# Current_control_iron.net
KiCad netlist of a schematic drawn in Altium Designer
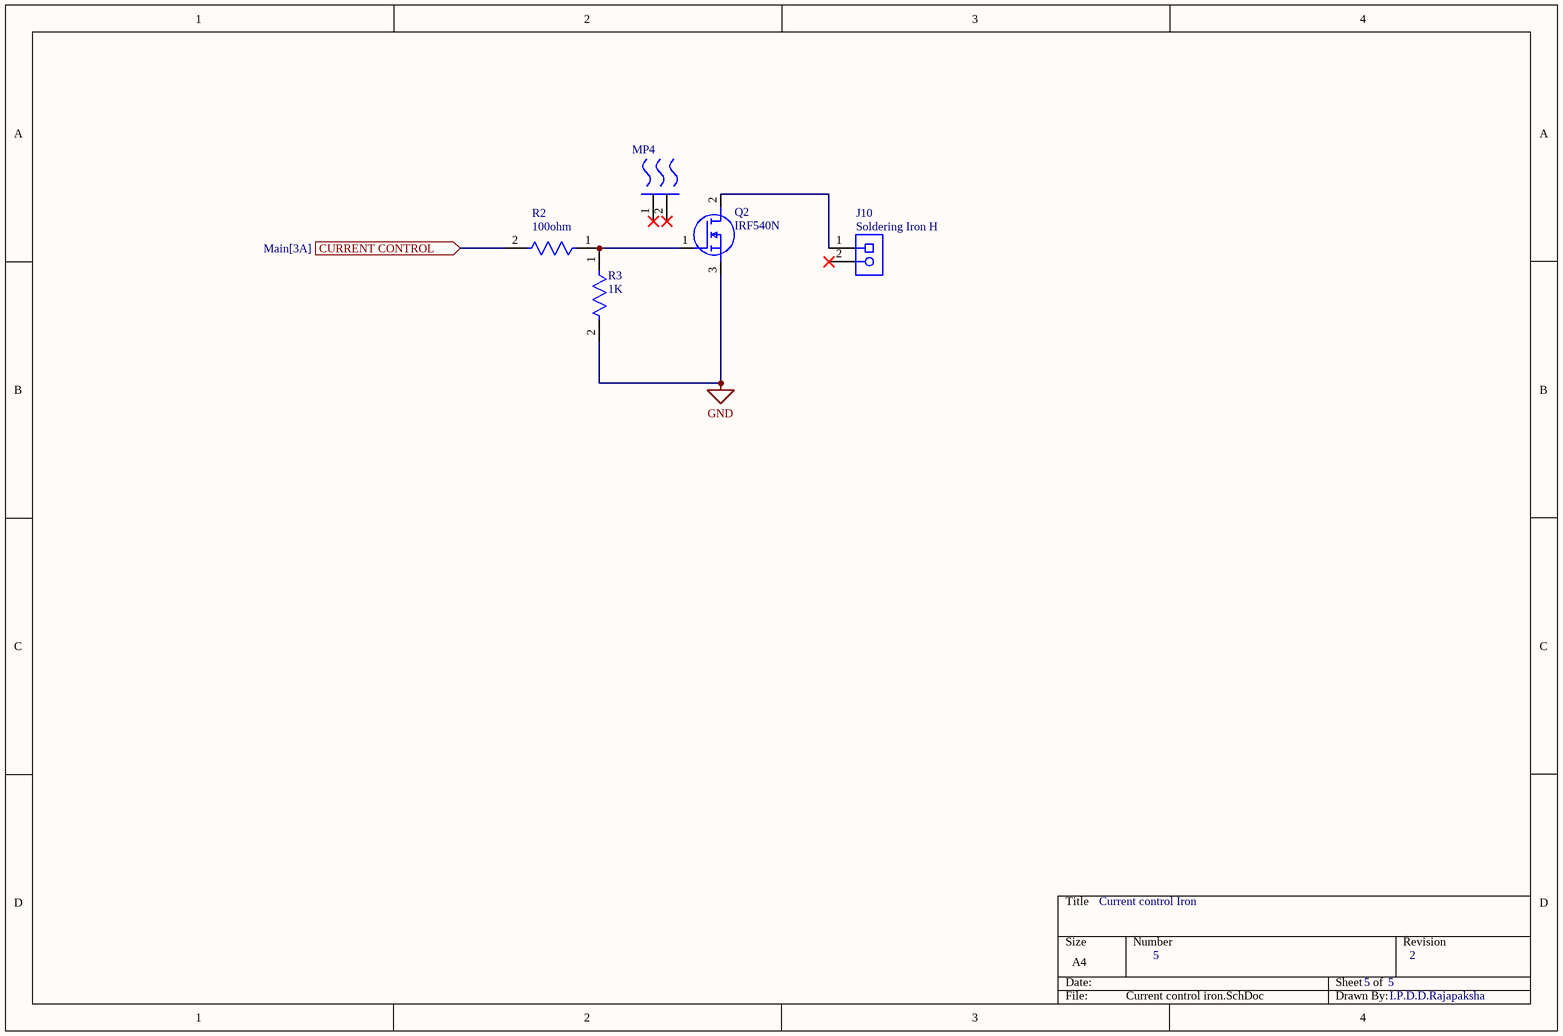
[diagram p0: Current control iron.SchDoc]

(export (version "E")
  (design (tool "Eeschema 10.0.6"))
  (components
    (comp (ref "J10")
      (value "1729128")
      (footprint "PHOE-1729128-2_V")
      (description "PCB Terminal Block, 13.5 A, 400 V, 2-Pin THD, RoHS, Bulk")
      (fields (field (name "MANUFACTURER") "Phoenix Contact") (field (name "PARAMETER 1") "Soldering Iron H"))
      (libsource (lib "Altium Content Vault") (part "CN-2P-F-R2"))
    )
    (comp (ref "MP4")
      (value "WV-T264-101E")
      (footprint "FP-WV-T264-101E-MFG")
      (description "HEATSINK W/CLIP FOR TO-264")
      (libsource (lib "Altium Content Vault") (part "df9a98908f0b1072c7a35a179da30c1"))
    )
    (comp (ref "Q2")
      (value "IRF540N")
      (footprint "SamacSys:TO254P469X1042X1967-3P")
      (description "MOSFET (N-Channel)")
      (libsource (lib "*") (part "IRF540N"))
    )
    (comp (ref "R2")
      (value "100ohm")
      (footprint "FP-CMF50-0")
      (description "CMF5073K200FHEB Res Metal Film 73.2K Ohm 1% 0.125W(1/8W) ±50ppm/°C Epoxy AXL T/R")
      (fields (field (name "TOLERANCE") "1%") (field (name "Comment") "CMF5073K200FHEB"))
      (libsource (lib "Altium Content Vault") (part "1029c3af85768c4190bb7ad29bc67b5"))
    )
    (comp (ref "R3")
      (value "1K")
      (footprint "FP-CMF50-0")
      (description "CMF5073K200FHEB Res Metal Film 73.2K Ohm 1% 0.125W(1/8W) ±50ppm/°C Epoxy AXL T/R")
      (fields (field (name "TOLERANCE") "1%") (field (name "Comment") "CMF5073K200FHEB"))
      (libsource (lib "Altium Content Vault") (part "1029c3af85768c4190bb7ad29bc67b5"))
    )
  )
  (nets
    (net (code "1") (name "/CURRENT CONTROL") (class "Default")
      (node (ref "R2") (pin "2") (pinfunction "2_2") (pintype "passive"))
    )
    (net (code "2") (name "GND") (class "Default")
      (node (ref "Q2") (pin "3") (pinfunction "S_3") (pintype "passive"))
      (node (ref "R3") (pin "2") (pinfunction "2_2") (pintype "passive"))
    )
    (net (code "3") (name "Net-(Q2-D)") (class "Default")
      (node (ref "J10") (pin "1") (pinfunction "1_1") (pintype "passive"))
      (node (ref "Q2") (pin "2") (pinfunction "D_2") (pintype "passive"))
    )
    (net (code "4") (name "Net-(Q2-G)") (class "Default")
      (node (ref "Q2") (pin "1") (pinfunction "G_1") (pintype "passive"))
      (node (ref "R2") (pin "1") (pinfunction "1_1") (pintype "passive"))
      (node (ref "R3") (pin "1") (pinfunction "1_1") (pintype "passive"))
    )
    (net (code "5") (name "unconnected-(J10-Pad2)") (class "Default")
      (node (ref "J10") (pin "2") (pinfunction "2_2") (pintype "passive+no_connect"))
    )
    (net (code "6") (name "unconnected-(MP4-MNT_1-Pad1)") (class "Default")
      (node (ref "MP4") (pin "1") (pinfunction "MNT_1_1") (pintype "passive+no_connect"))
    )
    (net (code "7") (name "unconnected-(MP4-MNT_2-Pad2)") (class "Default")
      (node (ref "MP4") (pin "2") (pinfunction "MNT_2_2") (pintype "passive+no_connect"))
    )
  )
)
